# AVR_ISP-Shield-v11.net
KiCad netlist of a schematic drawn in EAGLE
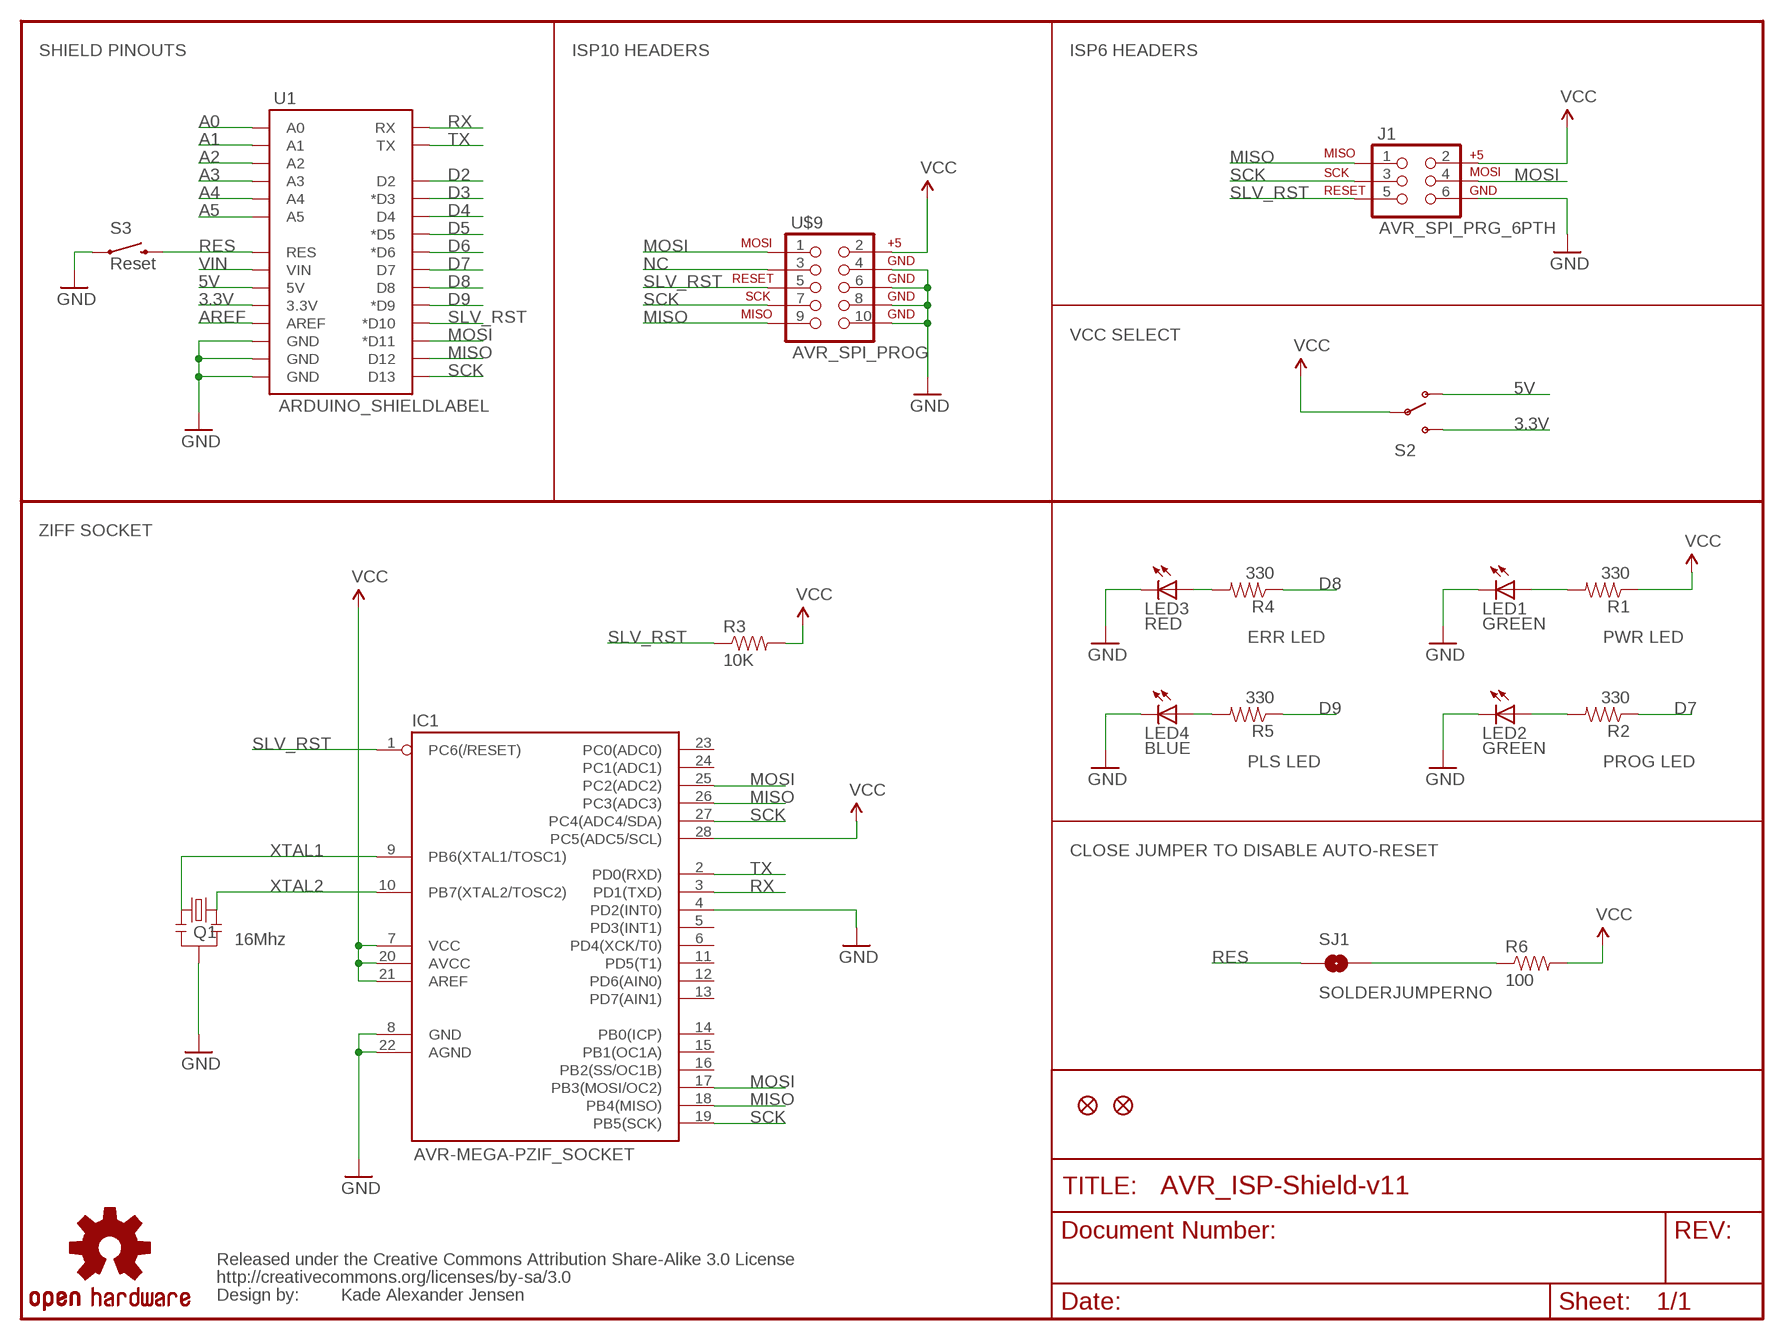
[diagram p0: schematic, sheet 1]

(export (version "E")
  (design (tool "Eeschema 10.0.6"))
  (components
    (comp (ref "$$U$1")
      (value "CREATIVE_COMMONS")
      (footprint "eagle-import:CREATIVE_COMMONS")
      (libsource (lib "eagle-import") (part "CREATIVE_COMMONS"))
    )
    (comp (ref "IC1")
      (value "AVR-MEGA-PZIF_SOCKET")
      (footprint "eagle-import:DIL28-3-ZIF_SOCKET")
      (libsource (lib "eagle-import") (part "AVR-MEGA8-PZIF_SOCKET"))
    )
    (comp (ref "J1")
      (value "AVR_SPI_PRG_6PTH")
      (footprint "eagle-import:2X3")
      (libsource (lib "eagle-import") (part "AVR_SPI_PRG_6PTH"))
    )
    (comp (ref "JP5")
      (value "FIDUCIAL1X2.5")
      (footprint "eagle-import:FIDUCIAL-1X2.5")
      (libsource (lib "eagle-import") (part "FIDUCIAL1X2.5"))
    )
    (comp (ref "JP6")
      (value "FIDUCIAL1X2.5")
      (footprint "eagle-import:FIDUCIAL-1X2.5")
      (libsource (lib "eagle-import") (part "FIDUCIAL1X2.5"))
    )
    (comp (ref "LED1")
      (value "GREEN")
      (footprint "eagle-import:LED-0603")
      (libsource (lib "eagle-import") (part "LED0603"))
    )
    (comp (ref "LED2")
      (value "GREEN")
      (footprint "eagle-import:LED-0603")
      (libsource (lib "eagle-import") (part "LED0603"))
    )
    (comp (ref "LED3")
      (value "RED")
      (footprint "eagle-import:LED-0603")
      (libsource (lib "eagle-import") (part "LED0603"))
    )
    (comp (ref "LED4")
      (value "BLUE")
      (footprint "eagle-import:LED-0603")
      (libsource (lib "eagle-import") (part "LED0603"))
    )
    (comp (ref "Q1")
      (value "8/16/20MHz")
      (footprint "eagle-import:RESONATOR-SMD")
      (libsource (lib "eagle-import") (part "RESONATORSMD"))
    )
    (comp (ref "R1")
      (value "330")
      (footprint "eagle-import:0402-RES")
      (libsource (lib "eagle-import") (part "RESISTOR0402-RES"))
    )
    (comp (ref "R2")
      (value "330")
      (footprint "eagle-import:0402-RES")
      (libsource (lib "eagle-import") (part "RESISTOR0402-RES"))
    )
    (comp (ref "R3")
      (value "10K")
      (footprint "eagle-import:0402-RES")
      (libsource (lib "eagle-import") (part "RESISTOR0402-RES"))
    )
    (comp (ref "R4")
      (value "330")
      (footprint "eagle-import:0402-RES")
      (libsource (lib "eagle-import") (part "RESISTOR0402-RES"))
    )
    (comp (ref "R5")
      (value "330")
      (footprint "eagle-import:0402-RES")
      (libsource (lib "eagle-import") (part "RESISTOR0402-RES"))
    )
    (comp (ref "R6")
      (value "100")
      (footprint "eagle-import:0402-RES")
      (libsource (lib "eagle-import") (part "RESISTOR0402-RES"))
    )
    (comp (ref "S2")
      (value "SWITCH-SPSTSMD")
      (footprint "eagle-import:AYZ0202")
      (libsource (lib "eagle-import") (part "SWITCH-SPSTSMD"))
    )
    (comp (ref "S3")
      (value "Reset")
      (footprint "eagle-import:TACTILE_SWITCH_SMD")
      (libsource (lib "eagle-import") (part "SWITCH-MOMENTARY-2SMD"))
    )
    (comp (ref "SJ1")
      (value "SOLDERJUMPERNO")
      (footprint "eagle-import:SJ_2S-NO")
      (libsource (lib "eagle-import") (part "SOLDERJUMPERNO"))
    )
    (comp (ref "U$4")
      (value "OSHW-LOGOS")
      (footprint "eagle-import:OSHW-LOGO-S")
      (libsource (lib "eagle-import") (part "OSHW-LOGOS"))
    )
    (comp (ref "U$9")
      (value "AVR_SPI_PROG")
      (footprint "eagle-import:AVR_ICSP")
      (libsource (lib "eagle-import") (part "AVR_SPI_PROG"))
    )
    (comp (ref "U1")
      (value "ARDUINO_SHIELDLABEL")
      (footprint "eagle-import:DUEMILANOVE_SHIELD")
      (libsource (lib "eagle-import") (part "ARDUINO_SHIELDLABEL"))
    )
  )
  (nets
    (net (code "1") (name "/3.3V") (class "Default")
      (node (ref "S2") (pin "3") (pinfunction "S_3") (pintype "passive"))
      (node (ref "U1") (pin "3.3V") (pinfunction "3.3V_3.3V") (pintype "bidirectional"))
    )
    (net (code "2") (name "/5V") (class "Default")
      (node (ref "S2") (pin "1") (pinfunction "O_1") (pintype "passive"))
      (node (ref "U1") (pin "5V") (pinfunction "5V_5V") (pintype "bidirectional"))
    )
    (net (code "3") (name "/A0") (class "Default")
      (node (ref "U1") (pin "A0") (pinfunction "A0_A0") (pintype "bidirectional"))
    )
    (net (code "4") (name "/A1") (class "Default")
      (node (ref "U1") (pin "A1") (pinfunction "A1_A1") (pintype "bidirectional"))
    )
    (net (code "5") (name "/A2") (class "Default")
      (node (ref "U1") (pin "A2") (pinfunction "A2_A2") (pintype "bidirectional"))
    )
    (net (code "6") (name "/A3") (class "Default")
      (node (ref "U1") (pin "A3") (pinfunction "A3_A3") (pintype "bidirectional"))
    )
    (net (code "7") (name "/A4") (class "Default")
      (node (ref "U1") (pin "A4") (pinfunction "A4_A4") (pintype "bidirectional"))
    )
    (net (code "8") (name "/A5") (class "Default")
      (node (ref "U1") (pin "A5") (pinfunction "A5_A5") (pintype "bidirectional"))
    )
    (net (code "9") (name "/AREF") (class "Default")
      (node (ref "U1") (pin "AREF") (pinfunction "AREF_AREF") (pintype "bidirectional"))
    )
    (net (code "10") (name "/D2") (class "Default")
      (node (ref "U1") (pin "D2") (pinfunction "D2_D2") (pintype "bidirectional"))
    )
    (net (code "11") (name "/D3") (class "Default")
      (node (ref "U1") (pin "D3") (pinfunction "*D3_D3") (pintype "bidirectional"))
    )
    (net (code "12") (name "/D4") (class "Default")
      (node (ref "U1") (pin "D4") (pinfunction "D4_D4") (pintype "bidirectional"))
    )
    (net (code "13") (name "/D5") (class "Default")
      (node (ref "U1") (pin "D5") (pinfunction "*D5_D5") (pintype "bidirectional"))
    )
    (net (code "14") (name "/D6") (class "Default")
      (node (ref "U1") (pin "D6") (pinfunction "*D6_D6") (pintype "bidirectional"))
    )
    (net (code "15") (name "/D7") (class "Default")
      (node (ref "R2") (pin "1") (pinfunction "1_1") (pintype "passive"))
      (node (ref "U1") (pin "D7") (pinfunction "D7_D7") (pintype "bidirectional"))
    )
    (net (code "16") (name "/D8") (class "Default")
      (node (ref "R4") (pin "1") (pinfunction "1_1") (pintype "passive"))
      (node (ref "U1") (pin "D8") (pinfunction "D8_D8") (pintype "bidirectional"))
    )
    (net (code "17") (name "/D9") (class "Default")
      (node (ref "R5") (pin "1") (pinfunction "1_1") (pintype "passive"))
      (node (ref "U1") (pin "D9") (pinfunction "*D9_D9") (pintype "bidirectional"))
    )
    (net (code "18") (name "/MISO") (class "Default")
      (node (ref "IC1") (pin "18") (pinfunction "PB4(MISO)_18") (pintype "bidirectional"))
      (node (ref "IC1") (pin "26") (pinfunction "PC3(ADC3)_26") (pintype "bidirectional"))
      (node (ref "J1") (pin "1") (pinfunction "1_1") (pintype "passive"))
      (node (ref "U$9") (pin "9") (pinfunction "9_9") (pintype "passive"))
      (node (ref "U1") (pin "D12") (pinfunction "D12_D12") (pintype "bidirectional"))
    )
    (net (code "19") (name "/MOSI") (class "Default")
      (node (ref "IC1") (pin "17") (pinfunction "PB3(MOSI/OC2)_17") (pintype "bidirectional"))
      (node (ref "IC1") (pin "25") (pinfunction "PC2(ADC2)_25") (pintype "bidirectional"))
      (node (ref "J1") (pin "4") (pinfunction "4_4") (pintype "passive"))
      (node (ref "U$9") (pin "1") (pinfunction "1_1") (pintype "passive"))
      (node (ref "U1") (pin "D11") (pinfunction "*D11_D11") (pintype "bidirectional"))
    )
    (net (code "20") (name "/NC") (class "Default")
      (node (ref "U$9") (pin "3") (pinfunction "3_3") (pintype "passive"))
    )
    (net (code "21") (name "/RES") (class "Default")
      (node (ref "S3") (pin "3") (pinfunction "2_3") (pintype "passive"))
      (node (ref "SJ1") (pin "1") (pinfunction "1_1") (pintype "passive"))
      (node (ref "U1") (pin "RES") (pinfunction "RES_RES") (pintype "bidirectional"))
    )
    (net (code "22") (name "/RX") (class "Default")
      (node (ref "IC1") (pin "3") (pinfunction "PD1(TXD)_3") (pintype "bidirectional"))
      (node (ref "U1") (pin "RX") (pinfunction "RX_RX") (pintype "bidirectional"))
    )
    (net (code "23") (name "/SCK") (class "Default")
      (node (ref "IC1") (pin "19") (pinfunction "PB5(SCK)_19") (pintype "bidirectional"))
      (node (ref "IC1") (pin "27") (pinfunction "PC4(ADC4/SDA)_27") (pintype "bidirectional"))
      (node (ref "J1") (pin "3") (pinfunction "3_3") (pintype "passive"))
      (node (ref "U$9") (pin "7") (pinfunction "7_7") (pintype "passive"))
      (node (ref "U1") (pin "D13") (pinfunction "D13_D13") (pintype "bidirectional"))
    )
    (net (code "24") (name "/SLV_RST") (class "Default")
      (node (ref "IC1") (pin "1") (pinfunction "PC6(/RESET)_1") (pintype "bidirectional"))
      (node (ref "J1") (pin "5") (pinfunction "5_5") (pintype "passive"))
      (node (ref "R3") (pin "1") (pinfunction "1_1") (pintype "passive"))
      (node (ref "U$9") (pin "5") (pinfunction "5_5") (pintype "passive"))
      (node (ref "U1") (pin "D10") (pinfunction "*D10_D10") (pintype "bidirectional"))
    )
    (net (code "25") (name "/TX") (class "Default")
      (node (ref "IC1") (pin "2") (pinfunction "PD0(RXD)_2") (pintype "bidirectional"))
      (node (ref "U1") (pin "TX") (pinfunction "TX_TX") (pintype "bidirectional"))
    )
    (net (code "26") (name "/VIN") (class "Default")
      (node (ref "U1") (pin "VIN") (pinfunction "VIN_VIN") (pintype "bidirectional"))
    )
    (net (code "27") (name "/XTAL1") (class "Default")
      (node (ref "IC1") (pin "9") (pinfunction "PB6(XTAL1/TOSC1)_9") (pintype "bidirectional"))
      (node (ref "Q1") (pin "3") (pinfunction "3_3") (pintype "passive"))
    )
    (net (code "28") (name "/XTAL2") (class "Default")
      (node (ref "IC1") (pin "10") (pinfunction "PB7(XTAL2/TOSC2)_10") (pintype "bidirectional"))
      (node (ref "Q1") (pin "1") (pinfunction "1_1") (pintype "passive"))
    )
    (net (code "29") (name "GND") (class "Default")
      (node (ref "IC1") (pin "22") (pinfunction "AGND_22") (pintype "bidirectional"))
      (node (ref "IC1") (pin "4") (pinfunction "PD2(INT0)_4") (pintype "bidirectional"))
      (node (ref "IC1") (pin "8") (pinfunction "GND_8") (pintype "bidirectional"))
      (node (ref "J1") (pin "6") (pinfunction "6_6") (pintype "passive"))
      (node (ref "LED1") (pin "C") (pinfunction "C_C") (pintype "passive"))
      (node (ref "LED2") (pin "C") (pinfunction "C_C") (pintype "passive"))
      (node (ref "LED3") (pin "C") (pinfunction "C_C") (pintype "passive"))
      (node (ref "LED4") (pin "C") (pinfunction "C_C") (pintype "passive"))
      (node (ref "Q1") (pin "2") (pinfunction "2_2") (pintype "passive"))
      (node (ref "S3") (pin "1") (pinfunction "1_1") (pintype "passive"))
      (node (ref "U$9") (pin "10") (pinfunction "10_10") (pintype "passive"))
      (node (ref "U$9") (pin "4") (pinfunction "4_4") (pintype "passive"))
      (node (ref "U$9") (pin "6") (pinfunction "6_6") (pintype "passive"))
      (node (ref "U$9") (pin "8") (pinfunction "8_8") (pintype "passive"))
      (node (ref "U1") (pin "GND@0") (pinfunction "GND_GND@0") (pintype "bidirectional"))
      (node (ref "U1") (pin "GND@1") (pinfunction "GND_GND@1") (pintype "bidirectional"))
      (node (ref "U1") (pin "GND@2") (pinfunction "GND_GND@2") (pintype "bidirectional"))
    )
    (net (code "30") (name "Net-(LED1-PadA)") (class "Default")
      (node (ref "LED1") (pin "A") (pinfunction "A_A") (pintype "passive"))
      (node (ref "R1") (pin "2") (pinfunction "2_2") (pintype "passive"))
    )
    (net (code "31") (name "Net-(LED2-PadA)") (class "Default")
      (node (ref "LED2") (pin "A") (pinfunction "A_A") (pintype "passive"))
      (node (ref "R2") (pin "2") (pinfunction "2_2") (pintype "passive"))
    )
    (net (code "32") (name "Net-(LED3-PadA)") (class "Default")
      (node (ref "LED3") (pin "A") (pinfunction "A_A") (pintype "passive"))
      (node (ref "R4") (pin "2") (pinfunction "2_2") (pintype "passive"))
    )
    (net (code "33") (name "Net-(LED4-PadA)") (class "Default")
      (node (ref "LED4") (pin "A") (pinfunction "A_A") (pintype "passive"))
      (node (ref "R5") (pin "2") (pinfunction "2_2") (pintype "passive"))
    )
    (net (code "34") (name "Net-(R6-Pad1)") (class "Default")
      (node (ref "R6") (pin "1") (pinfunction "1_1") (pintype "passive"))
      (node (ref "SJ1") (pin "2") (pinfunction "2_2") (pintype "passive"))
    )
    (net (code "35") (name "VCC") (class "Default")
      (node (ref "IC1") (pin "20") (pinfunction "AVCC_20") (pintype "bidirectional"))
      (node (ref "IC1") (pin "21") (pinfunction "AREF_21") (pintype "bidirectional"))
      (node (ref "IC1") (pin "28") (pinfunction "PC5(ADC5/SCL)_28") (pintype "bidirectional"))
      (node (ref "IC1") (pin "7") (pinfunction "VCC_7") (pintype "bidirectional"))
      (node (ref "J1") (pin "2") (pinfunction "2_2") (pintype "passive"))
      (node (ref "R1") (pin "1") (pinfunction "1_1") (pintype "passive"))
      (node (ref "R3") (pin "2") (pinfunction "2_2") (pintype "passive"))
      (node (ref "R6") (pin "2") (pinfunction "2_2") (pintype "passive"))
      (node (ref "S2") (pin "2") (pinfunction "P_2") (pintype "passive"))
      (node (ref "U$9") (pin "2") (pinfunction "2_2") (pintype "passive"))
    )
    (net (code "36") (name "unconnected-(IC1-PB0(ICP)-Pad14)") (class "Default")
      (node (ref "IC1") (pin "14") (pinfunction "PB0(ICP)_14") (pintype "bidirectional"))
    )
    (net (code "37") (name "unconnected-(IC1-PB1(OC1A)-Pad15)") (class "Default")
      (node (ref "IC1") (pin "15") (pinfunction "PB1(OC1A)_15") (pintype "bidirectional"))
    )
    (net (code "38") (name "unconnected-(IC1-PB2(SS{slash}OC1B)-Pad16)") (class "Default")
      (node (ref "IC1") (pin "16") (pinfunction "PB2(SS/OC1B)_16") (pintype "bidirectional"))
    )
    (net (code "39") (name "unconnected-(IC1-PC0(ADC0)-Pad23)") (class "Default")
      (node (ref "IC1") (pin "23") (pinfunction "PC0(ADC0)_23") (pintype "bidirectional"))
    )
    (net (code "40") (name "unconnected-(IC1-PC1(ADC1)-Pad24)") (class "Default")
      (node (ref "IC1") (pin "24") (pinfunction "PC1(ADC1)_24") (pintype "bidirectional"))
    )
    (net (code "41") (name "unconnected-(IC1-PD3(INT1)-Pad5)") (class "Default")
      (node (ref "IC1") (pin "5") (pinfunction "PD3(INT1)_5") (pintype "bidirectional"))
    )
    (net (code "42") (name "unconnected-(IC1-PD4(XCK{slash}T0)-Pad6)") (class "Default")
      (node (ref "IC1") (pin "6") (pinfunction "PD4(XCK/T0)_6") (pintype "bidirectional"))
    )
    (net (code "43") (name "unconnected-(IC1-PD5(T1)-Pad11)") (class "Default")
      (node (ref "IC1") (pin "11") (pinfunction "PD5(T1)_11") (pintype "bidirectional"))
    )
    (net (code "44") (name "unconnected-(IC1-PD6(AIN0)-Pad12)") (class "Default")
      (node (ref "IC1") (pin "12") (pinfunction "PD6(AIN0)_12") (pintype "bidirectional"))
    )
    (net (code "45") (name "unconnected-(IC1-PD7(AIN1)-Pad13)") (class "Default")
      (node (ref "IC1") (pin "13") (pinfunction "PD7(AIN1)_13") (pintype "bidirectional"))
    )
  )
)
